# 467444_130_3_2-A.net
KiCad netlist of a schematic drawn in Altium Designer
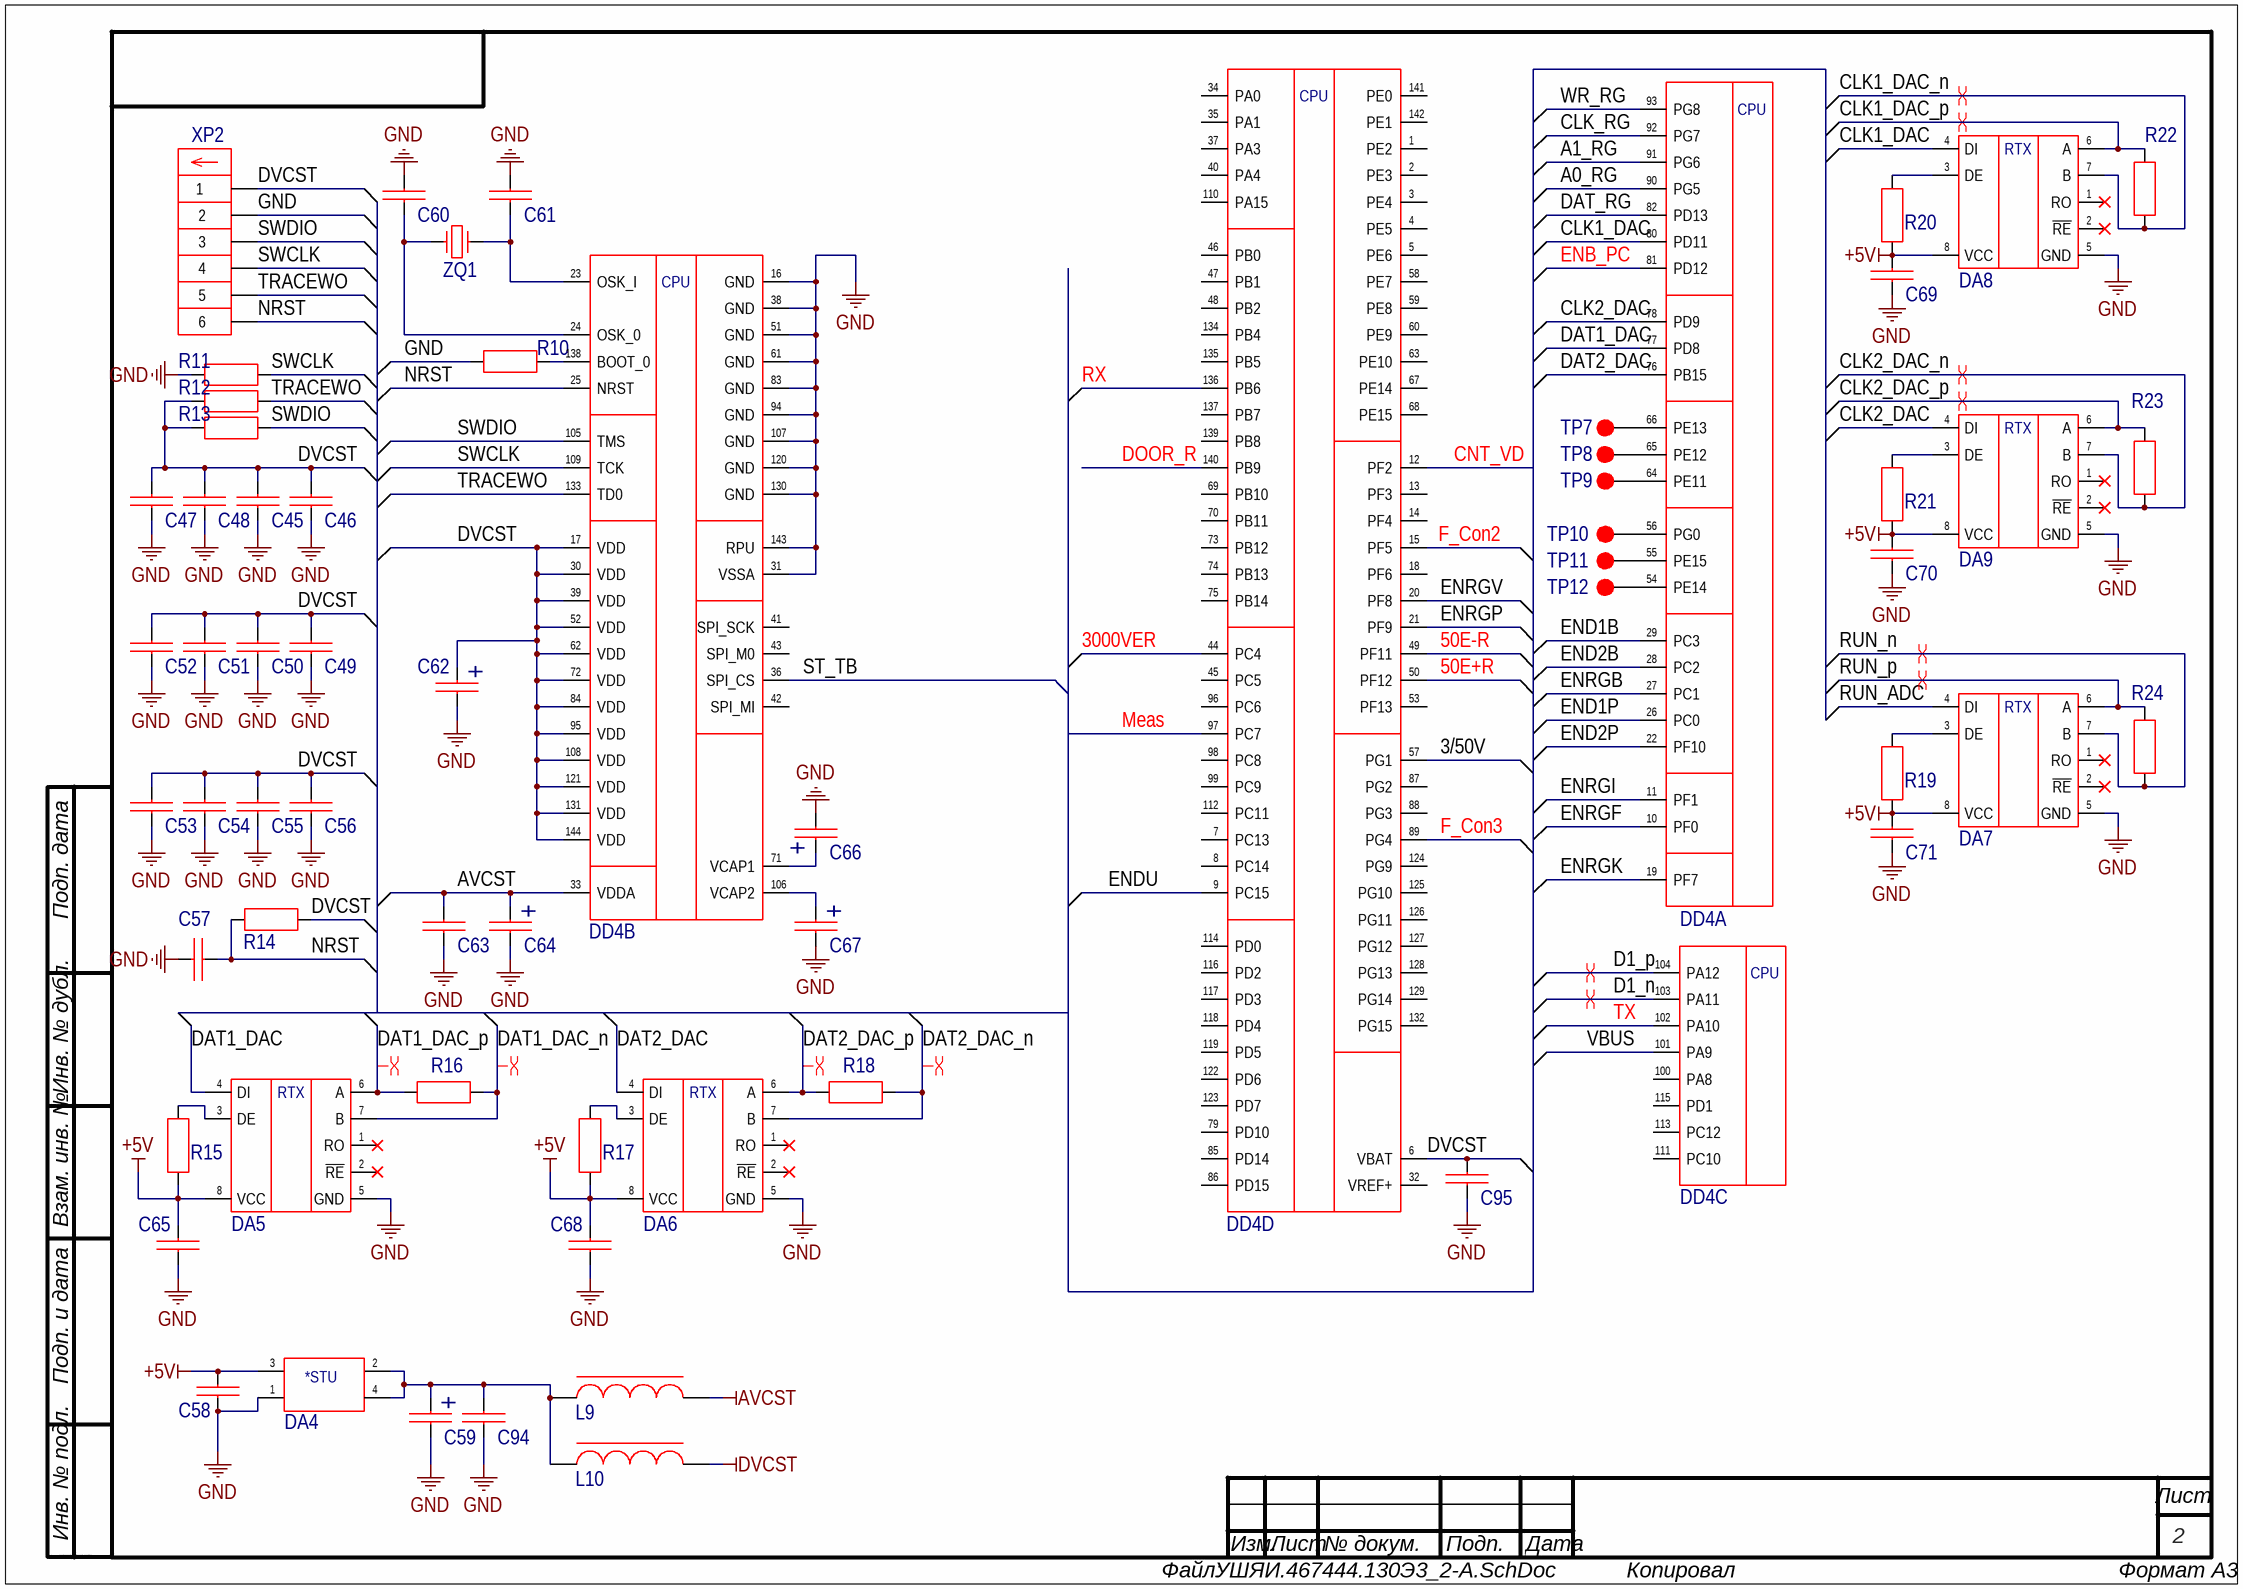
[diagram p0: УШЯИ.467444.130Э3_2-A.SchDoc]

(export (version "E")
  (design (tool "Eeschema 10.0.6"))
  (components
    (comp (ref "C45")
      (value "0,1 µF")
      (footprint "C_0805 [2012 Metric]")
      (description "Неполярный конденсатор")
      (fields (field (name "MANUFACTURER") "Murata") (field (name "VOLTAGE") "50V"))
      (libsource (lib "lib") (part "C_const"))
    )
    (comp (ref "C46")
      (value "0,1 µF")
      (footprint "C_0805 [2012 Metric]")
      (description "Неполярный конденсатор")
      (fields (field (name "MANUFACTURER") "Murata") (field (name "VOLTAGE") "50V"))
      (libsource (lib "lib") (part "C_const"))
    )
    (comp (ref "C47")
      (value "0,1 µF")
      (footprint "C_0805 [2012 Metric]")
      (description "Неполярный конденсатор")
      (fields (field (name "MANUFACTURER") "Murata") (field (name "VOLTAGE") "50V"))
      (libsource (lib "lib") (part "C_const"))
    )
    (comp (ref "C48")
      (value "0,1 µF")
      (footprint "C_0805 [2012 Metric]")
      (description "Неполярный конденсатор")
      (fields (field (name "MANUFACTURER") "Murata") (field (name "VOLTAGE") "50V"))
      (libsource (lib "lib") (part "C_const"))
    )
    (comp (ref "C49")
      (value "0,1 µF")
      (footprint "C_0805 [2012 Metric]")
      (description "Неполярный конденсатор")
      (fields (field (name "MANUFACTURER") "Murata") (field (name "VOLTAGE") "50V"))
      (libsource (lib "lib") (part "C_const"))
    )
    (comp (ref "C50")
      (value "0,1 µF")
      (footprint "C_0805 [2012 Metric]")
      (description "Неполярный конденсатор")
      (fields (field (name "MANUFACTURER") "Murata") (field (name "VOLTAGE") "50V"))
      (libsource (lib "lib") (part "C_const"))
    )
    (comp (ref "C51")
      (value "0,1 µF")
      (footprint "C_0805 [2012 Metric]")
      (description "Неполярный конденсатор")
      (fields (field (name "MANUFACTURER") "Murata") (field (name "VOLTAGE") "50V"))
      (libsource (lib "lib") (part "C_const"))
    )
    (comp (ref "C52")
      (value "0,1 µF")
      (footprint "C_0805 [2012 Metric]")
      (description "Неполярный конденсатор")
      (fields (field (name "MANUFACTURER") "Murata") (field (name "VOLTAGE") "50V"))
      (libsource (lib "lib") (part "C_const"))
    )
    (comp (ref "C53")
      (value "0,1 µF")
      (footprint "C_0805 [2012 Metric]")
      (description "Неполярный конденсатор")
      (fields (field (name "MANUFACTURER") "Murata") (field (name "VOLTAGE") "50V"))
      (libsource (lib "lib") (part "C_const"))
    )
    (comp (ref "C54")
      (value "0,1 µF")
      (footprint "C_0805 [2012 Metric]")
      (description "Неполярный конденсатор")
      (fields (field (name "MANUFACTURER") "Murata") (field (name "VOLTAGE") "50V"))
      (libsource (lib "lib") (part "C_const"))
    )
    (comp (ref "C55")
      (value "0,1 µF")
      (footprint "C_0805 [2012 Metric]")
      (description "Неполярный конденсатор")
      (fields (field (name "MANUFACTURER") "Murata") (field (name "VOLTAGE") "50V"))
      (libsource (lib "lib") (part "C_const"))
    )
    (comp (ref "C56")
      (value "0,1 µF")
      (footprint "C_0805 [2012 Metric]")
      (description "Неполярный конденсатор")
      (fields (field (name "MANUFACTURER") "Murata") (field (name "VOLTAGE") "50V"))
      (libsource (lib "lib") (part "C_const"))
    )
    (comp (ref "C57")
      (value "0,1 µF")
      (footprint "C_0805 [2012 Metric]")
      (description "Неполярный конденсатор")
      (fields (field (name "MANUFACTURER") "Murata") (field (name "VOLTAGE") "50V"))
      (libsource (lib "lib") (part "C_const"))
    )
    (comp (ref "C58")
      (value "0,1 µF")
      (footprint "C_0805 [2012 Metric]")
      (description "Неполярный конденсатор")
      (fields (field (name "MANUFACTURER") "Murata") (field (name "VOLTAGE") "50V"))
      (libsource (lib "lib") (part "C_const"))
    )
    (comp (ref "C59")
      (value "4,7 µF")
      (footprint "C+_1210 [3528-21 Metric]")
      (description "Полярный конденсатор")
      (fields (field (name "MANUFACTURER") "KYOCERA AVX") (field (name "VOLTAGE") "20V\r\n10V"))
      (libsource (lib "lib") (part "C_electrolytic"))
    )
    (comp (ref "C60")
      (value "20 pF")
      (footprint "C_0805 [2012 Metric]")
      (description "Неполярный конденсатор")
      (fields (field (name "MANUFACTURER") "Murata") (field (name "VOLTAGE") "50V"))
      (libsource (lib "lib") (part "C_const"))
    )
    (comp (ref "C61")
      (value "20 pF")
      (footprint "C_0805 [2012 Metric]")
      (description "Неполярный конденсатор")
      (fields (field (name "MANUFACTURER") "Murata") (field (name "VOLTAGE") "50V"))
      (libsource (lib "lib") (part "C_const"))
    )
    (comp (ref "C62")
      (value "10 µF")
      (footprint "C+_1210 [3528-21 Metric]")
      (description "Полярный конденсатор")
      (fields (field (name "MANUFACTURER") "KYOCERA AVX") (field (name "VOLTAGE") "20V\r\n10V"))
      (libsource (lib "lib") (part "C_electrolytic"))
    )
    (comp (ref "C63")
      (value "0,1 µF")
      (footprint "C_0805 [2012 Metric]")
      (description "Неполярный конденсатор")
      (fields (field (name "MANUFACTURER") "Murata") (field (name "VOLTAGE") "50V"))
      (libsource (lib "lib") (part "C_const"))
    )
    (comp (ref "C64")
      (value "10 µF")
      (footprint "C+_1210 [3528-21 Metric]")
      (description "Полярный конденсатор")
      (fields (field (name "MANUFACTURER") "KYOCERA AVX") (field (name "VOLTAGE") "20V\r\n10V"))
      (libsource (lib "lib") (part "C_electrolytic"))
    )
    (comp (ref "C65")
      (value "0,1 µF")
      (footprint "C_0805 [2012 Metric]")
      (description "Неполярный конденсатор")
      (fields (field (name "MANUFACTURER") "Murata") (field (name "VOLTAGE") "50V"))
      (libsource (lib "lib") (part "C_const"))
    )
    (comp (ref "C66")
      (value "2,2 µF")
      (footprint "C+_1206 [3216-18 Metric]")
      (description "Полярный конденсатор")
      (fields (field (name "MANUFACTURER") "AVX") (field (name "VOLTAGE") "16V\r\n10V"))
      (libsource (lib "lib") (part "C_electrolytic"))
    )
    (comp (ref "C67")
      (value "2,2 µF")
      (footprint "C+_1206 [3216-18 Metric]")
      (description "Полярный конденсатор")
      (fields (field (name "MANUFACTURER") "AVX") (field (name "VOLTAGE") "16V\r\n10V"))
      (libsource (lib "lib") (part "C_electrolytic"))
    )
    (comp (ref "C68")
      (value "0,1 µF")
      (footprint "C_0805 [2012 Metric]")
      (description "Неполярный конденсатор")
      (fields (field (name "MANUFACTURER") "Murata") (field (name "VOLTAGE") "50V"))
      (libsource (lib "lib") (part "C_const"))
    )
    (comp (ref "C69")
      (value "0,1 µF")
      (footprint "C_0805 [2012 Metric]")
      (description "Неполярный конденсатор")
      (fields (field (name "MANUFACTURER") "Murata") (field (name "VOLTAGE") "50V"))
      (libsource (lib "lib") (part "C_const"))
    )
    (comp (ref "C70")
      (value "0,1 µF")
      (footprint "C_0805 [2012 Metric]")
      (description "Неполярный конденсатор")
      (fields (field (name "MANUFACTURER") "Murata") (field (name "VOLTAGE") "50V"))
      (libsource (lib "lib") (part "C_const"))
    )
    (comp (ref "C71")
      (value "0,1 µF")
      (footprint "C_0805 [2012 Metric]")
      (description "Неполярный конденсатор")
      (fields (field (name "MANUFACTURER") "Murata") (field (name "VOLTAGE") "50V"))
      (libsource (lib "lib") (part "C_const"))
    )
    (comp (ref "C94")
      (value "0,1 µF")
      (footprint "C_0805 [2012 Metric]")
      (description "Неполярный конденсатор")
      (fields (field (name "MANUFACTURER") "Murata") (field (name "VOLTAGE") "25V"))
      (libsource (lib "lib") (part "C_const"))
    )
    (comp (ref "C95")
      (value "0,1 µF")
      (footprint "C_0805 [2012 Metric]")
      (description "Неполярный конденсатор")
      (fields (field (name "MANUFACTURER") "Murata") (field (name "VOLTAGE") "50V"))
      (libsource (lib "lib") (part "C_const"))
    )
    (comp (ref "DA4")
      (value "LD1117AS33TR")
      (footprint "SOT-223")
      (description "IC, Fixed LDO Voltage Regulator, 5.3V to 10V, 1.15V Dropout, 3.3Vout, 1Aout")
      (fields (field (name "MANUFACTURER") "STMicroelectronics"))
      (libsource (lib "lib") (part "VolReg_LD1117AS33TR"))
    )
    (comp (ref "DA5")
      (value "ADM483AR")
      (footprint "SOIC-8_1.27_5x4x1.75")
      (description "IC, Transceiver, RS422/RS485, 1 Driver, 1 Receiver, 4.75 V to 5.25 V, -40°C to 125°C")
      (fields (field (name "MANUFACTURER") "Analog Devices"))
      (libsource (lib "lib") (part "ADM483"))
    )
    (comp (ref "DA6")
      (value "ADM483AR")
      (footprint "SOIC-8_1.27_5x4x1.75")
      (description "IC, Transceiver, RS422/RS485, 1 Driver, 1 Receiver, 4.75 V to 5.25 V, -40°C to 125°C")
      (fields (field (name "MANUFACTURER") "Analog Devices"))
      (libsource (lib "lib") (part "ADM483"))
    )
    (comp (ref "DA7")
      (value "ADM483AR")
      (footprint "SOIC-8_1.27_5x4x1.75")
      (description "IC, Transceiver, RS422/RS485, 1 Driver, 1 Receiver, 4.75 V to 5.25 V, -40°C to 125°C")
      (fields (field (name "MANUFACTURER") "Analog Devices"))
      (libsource (lib "lib") (part "ADM483"))
    )
    (comp (ref "DA8")
      (value "ADM483AR")
      (footprint "SOIC-8_1.27_5x4x1.75")
      (description "IC, Transceiver, RS422/RS485, 1 Driver, 1 Receiver, 4.75 V to 5.25 V, -40°C to 125°C")
      (fields (field (name "MANUFACTURER") "Analog Devices"))
      (libsource (lib "lib") (part "ADM483"))
    )
    (comp (ref "DA9")
      (value "ADM483AR")
      (footprint "SOIC-8_1.27_5x4x1.75")
      (description "IC, Transceiver, RS422/RS485, 1 Driver, 1 Receiver, 4.75 V to 5.25 V, -40°C to 125°C")
      (fields (field (name "MANUFACTURER") "Analog Devices"))
      (libsource (lib "lib") (part "ADM483"))
    )
    (comp (ref "DD4")
      (value "STM32F429VIT6STM32F407ZGTx")
      (footprint "QFP-144[20x20]_0.5_22x22x1.6")
      (description "IC, ARM Cortex-M4, 168 MHz, 1 MB ROM, 192 kB RAM, -40°C to 85°C")
      (fields (field (name "MANUFACTURER") "STMicroelectronics"))
      (libsource (lib "lib") (part "STM32F407"))
    )
    (comp (ref "L9")
      (value "~")
      (footprint "IND_0805 [2012 Metric]")
      (fields (field (name "MANUFACTURER") "Vishay") (field (name "TOLERANCE") "±25%"))
      (libsource (lib "lib") (part "IND_ferromagnetic/ferrite_core"))
    )
    (comp (ref "L10")
      (value "~")
      (footprint "IND_0805 [2012 Metric]")
      (fields (field (name "MANUFACTURER") "Vishay") (field (name "TOLERANCE") "±25%"))
      (libsource (lib "lib") (part "IND_ferromagnetic/ferrite_core"))
    )
    (comp (ref "R10")
      (value "10k")
      (footprint "R_0805 [2012 Metric]")
      (fields (field (name "TOLERANCE") "±5%"))
      (libsource (lib "lib") (part "R_Const"))
    )
    (comp (ref "R11")
      (value "10k")
      (footprint "R_0805 [2012 Metric]")
      (fields (field (name "TOLERANCE") "±5%"))
      (libsource (lib "lib") (part "R_Const"))
    )
    (comp (ref "R12")
      (value "10k")
      (footprint "R_0805 [2012 Metric]")
      (fields (field (name "TOLERANCE") "±5%"))
      (libsource (lib "lib") (part "R_Const"))
    )
    (comp (ref "R13")
      (value "10k")
      (footprint "R_0805 [2012 Metric]")
      (fields (field (name "TOLERANCE") "±5%"))
      (libsource (lib "lib") (part "R_Const"))
    )
    (comp (ref "R14")
      (value "10k")
      (footprint "R_0805 [2012 Metric]")
      (fields (field (name "TOLERANCE") "±5%"))
      (libsource (lib "lib") (part "R_Const"))
    )
    (comp (ref "R15")
      (value "10k")
      (footprint "R_0805 [2012 Metric]")
      (fields (field (name "TOLERANCE") "±5%"))
      (libsource (lib "lib") (part "R_Const"))
    )
    (comp (ref "R16")
      (value "100R")
      (footprint "R_0805 [2012 Metric]")
      (fields (field (name "TOLERANCE") "±5%"))
      (libsource (lib "lib") (part "R_Const"))
    )
    (comp (ref "R17")
      (value "10k")
      (footprint "R_0805 [2012 Metric]")
      (fields (field (name "TOLERANCE") "±5%"))
      (libsource (lib "lib") (part "R_Const"))
    )
    (comp (ref "R18")
      (value "100R")
      (footprint "R_0805 [2012 Metric]")
      (fields (field (name "TOLERANCE") "±5%"))
      (libsource (lib "lib") (part "R_Const"))
    )
    (comp (ref "R19")
      (value "10k")
      (footprint "R_0805 [2012 Metric]")
      (fields (field (name "TOLERANCE") "±5%"))
      (libsource (lib "lib") (part "R_Const"))
    )
    (comp (ref "R20")
      (value "10k")
      (footprint "R_0805 [2012 Metric]")
      (fields (field (name "TOLERANCE") "±5%"))
      (libsource (lib "lib") (part "R_Const"))
    )
    (comp (ref "R21")
      (value "10k")
      (footprint "R_0805 [2012 Metric]")
      (fields (field (name "TOLERANCE") "±5%"))
      (libsource (lib "lib") (part "R_Const"))
    )
    (comp (ref "R22")
      (value "100R")
      (footprint "R_0805 [2012 Metric]")
      (fields (field (name "TOLERANCE") "±5%"))
      (libsource (lib "lib") (part "R_Const"))
    )
    (comp (ref "R23")
      (value "100R")
      (footprint "R_0805 [2012 Metric]")
      (fields (field (name "TOLERANCE") "±5%"))
      (libsource (lib "lib") (part "R_Const"))
    )
    (comp (ref "R24")
      (value "100R")
      (footprint "R_0805 [2012 Metric]")
      (fields (field (name "TOLERANCE") "±5%"))
      (libsource (lib "lib") (part "R_Const"))
    )
    (comp (ref "TP7") (value "~") (footprint "DSP_1.3") (libsource (lib "lib") (part "TP")))
    (comp (ref "TP8") (value "~") (footprint "DSP_1.3") (libsource (lib "lib") (part "TP")))
    (comp (ref "TP9") (value "~") (footprint "DSP_1.3") (libsource (lib "lib") (part "TP")))
    (comp (ref "TP10") (value "~") (footprint "DSP_1.3") (libsource (lib "lib") (part "TP")))
    (comp (ref "TP11") (value "~") (footprint "DSP_1.3") (libsource (lib "lib") (part "TP")))
    (comp (ref "TP12") (value "~") (footprint "DSP_1.3") (libsource (lib "lib") (part "TP")))
    (comp (ref "XP2")
      (value "AMPMODU II 280372-2")
      (footprint "AMP II-280372-2")
      (description "Male, 6 pin, 1 row, Vertical, Board-to-Board, 2.54 mm")
      (fields (field (name "MANUFACTURER") "TE Connectivity"))
      (libsource (lib "lib") (part "M_6"))
    )
    (comp (ref "ZQ1")
      (value "Q 25.0JXS63-12-30/30-FU")
      (footprint "JXS63")
      (fields (field (name "MANUFACTURER") "Jauch Quartz GmbH"))
      (libsource (lib "lib") (part "Rezonator_JXS63"))
    )
  )
  (nets
    (net (code "1") (name "+5V") (class "Default")
      (node (ref "C58") (pin "1") (pinfunction "1_1") (pintype "passive"))
      (node (ref "C65") (pin "2") (pinfunction "2_2") (pintype "passive"))
      (node (ref "C68") (pin "2") (pinfunction "2_2") (pintype "passive"))
      (node (ref "C69") (pin "2") (pinfunction "2_2") (pintype "passive"))
      (node (ref "C70") (pin "2") (pinfunction "2_2") (pintype "passive"))
      (node (ref "C71") (pin "2") (pinfunction "2_2") (pintype "passive"))
      (node (ref "DA4") (pin "3") (pinfunction "VIN_3") (pintype "passive"))
      (node (ref "DA5") (pin "8") (pinfunction "VCC_8") (pintype "passive"))
      (node (ref "DA6") (pin "8") (pinfunction "VCC_8") (pintype "passive"))
      (node (ref "DA7") (pin "8") (pinfunction "VCC_8") (pintype "passive"))
      (node (ref "DA8") (pin "8") (pinfunction "VCC_8") (pintype "passive"))
      (node (ref "DA9") (pin "8") (pinfunction "VCC_8") (pintype "passive"))
      (node (ref "R15") (pin "1") (pinfunction "1_1") (pintype "passive"))
      (node (ref "R17") (pin "1") (pinfunction "1_1") (pintype "passive"))
      (node (ref "R19") (pin "1") (pinfunction "1_1") (pintype "passive"))
      (node (ref "R20") (pin "1") (pinfunction "1_1") (pintype "passive"))
      (node (ref "R21") (pin "1") (pinfunction "1_1") (pintype "passive"))
    )
    (net (code "2") (name "/3{slash}50V") (class "Default")
      (node (ref "DD4") (pin "57") (pinfunction "PG1_57") (pintype "passive"))
    )
    (net (code "3") (name "/50E+R") (class "Default")
      (node (ref "DD4") (pin "50") (pinfunction "PF12_50") (pintype "passive"))
    )
    (net (code "4") (name "/50E-R") (class "Default")
      (node (ref "DD4") (pin "49") (pinfunction "PF11_49") (pintype "passive"))
    )
    (net (code "5") (name "/3000VER") (class "Default")
      (node (ref "DD4") (pin "44") (pinfunction "PC4_44") (pintype "passive"))
    )
    (net (code "6") (name "/A0_RG") (class "Default")
      (node (ref "DD4") (pin "90") (pinfunction "PG5_90") (pintype "passive"))
    )
    (net (code "7") (name "/A1_RG") (class "Default")
      (node (ref "DD4") (pin "91") (pinfunction "PG6_91") (pintype "passive"))
    )
    (net (code "8") (name "/CLK1_DAC") (class "Default")
      (node (ref "DA8") (pin "4") (pinfunction "DI_4") (pintype "passive"))
      (node (ref "DD4") (pin "80") (pinfunction "PD11_80") (pintype "passive"))
    )
    (net (code "9") (name "/CLK1_DAC_n") (class "Default")
      (node (ref "DA8") (pin "7") (pinfunction "B_7") (pintype "passive"))
      (node (ref "R22") (pin "1") (pinfunction "1_1") (pintype "passive"))
    )
    (net (code "10") (name "/CLK1_DAC_p") (class "Default")
      (node (ref "DA8") (pin "6") (pinfunction "A_6") (pintype "passive"))
      (node (ref "R22") (pin "2") (pinfunction "2_2") (pintype "passive"))
    )
    (net (code "11") (name "/CLK2_DAC") (class "Default")
      (node (ref "DA9") (pin "4") (pinfunction "DI_4") (pintype "passive"))
      (node (ref "DD4") (pin "78") (pinfunction "PD9_78") (pintype "passive"))
    )
    (net (code "12") (name "/CLK2_DAC_n") (class "Default")
      (node (ref "DA9") (pin "7") (pinfunction "B_7") (pintype "passive"))
      (node (ref "R23") (pin "1") (pinfunction "1_1") (pintype "passive"))
    )
    (net (code "13") (name "/CLK2_DAC_p") (class "Default")
      (node (ref "DA9") (pin "6") (pinfunction "A_6") (pintype "passive"))
      (node (ref "R23") (pin "2") (pinfunction "2_2") (pintype "passive"))
    )
    (net (code "14") (name "/CLK_RG") (class "Default")
      (node (ref "DD4") (pin "92") (pinfunction "PG7_92") (pintype "passive"))
    )
    (net (code "15") (name "/CNT_VD") (class "Default")
      (node (ref "DD4") (pin "12") (pinfunction "PF2_12") (pintype "passive"))
    )
    (net (code "16") (name "/D1_n") (class "Default")
      (node (ref "DD4") (pin "103") (pinfunction "PA11_103") (pintype "passive"))
    )
    (net (code "17") (name "/D1_p") (class "Default")
      (node (ref "DD4") (pin "104") (pinfunction "PA12_104") (pintype "passive"))
    )
    (net (code "18") (name "/DAT1_DAC") (class "Default")
      (node (ref "DA5") (pin "4") (pinfunction "DI_4") (pintype "passive"))
      (node (ref "DD4") (pin "77") (pinfunction "PD8_77") (pintype "passive"))
    )
    (net (code "19") (name "/DAT1_DAC_n") (class "Default")
      (node (ref "DA5") (pin "7") (pinfunction "B_7") (pintype "passive"))
      (node (ref "R16") (pin "2") (pinfunction "2_2") (pintype "passive"))
    )
    (net (code "20") (name "/DAT1_DAC_p") (class "Default")
      (node (ref "DA5") (pin "6") (pinfunction "A_6") (pintype "passive"))
      (node (ref "R16") (pin "1") (pinfunction "1_1") (pintype "passive"))
    )
    (net (code "21") (name "/DAT2_DAC") (class "Default")
      (node (ref "DA6") (pin "4") (pinfunction "DI_4") (pintype "passive"))
      (node (ref "DD4") (pin "76") (pinfunction "PB15_76") (pintype "passive"))
    )
    (net (code "22") (name "/DAT2_DAC_n") (class "Default")
      (node (ref "DA6") (pin "7") (pinfunction "B_7") (pintype "passive"))
      (node (ref "R18") (pin "2") (pinfunction "2_2") (pintype "passive"))
    )
    (net (code "23") (name "/DAT2_DAC_p") (class "Default")
      (node (ref "DA6") (pin "6") (pinfunction "A_6") (pintype "passive"))
      (node (ref "R18") (pin "1") (pinfunction "1_1") (pintype "passive"))
    )
    (net (code "24") (name "/DAT_RG") (class "Default")
      (node (ref "DD4") (pin "82") (pinfunction "PD13_82") (pintype "passive"))
    )
    (net (code "25") (name "/DOOR_R") (class "Default")
      (node (ref "DD4") (pin "140") (pinfunction "PB9_140") (pintype "passive"))
    )
    (net (code "26") (name "/ENB_PC") (class "Default")
      (node (ref "DD4") (pin "81") (pinfunction "PD12_81") (pintype "passive"))
    )
    (net (code "27") (name "/END1B") (class "Default")
      (node (ref "DD4") (pin "29") (pinfunction "PC3_29") (pintype "passive"))
    )
    (net (code "28") (name "/END1P") (class "Default")
      (node (ref "DD4") (pin "26") (pinfunction "PC0_26") (pintype "passive"))
    )
    (net (code "29") (name "/END2B") (class "Default")
      (node (ref "DD4") (pin "28") (pinfunction "PC2_28") (pintype "passive"))
    )
    (net (code "30") (name "/END2P") (class "Default")
      (node (ref "DD4") (pin "22") (pinfunction "PF10_22") (pintype "passive"))
    )
    (net (code "31") (name "/ENDU") (class "Default")
      (node (ref "DD4") (pin "9") (pinfunction "PC15_9") (pintype "passive"))
    )
    (net (code "32") (name "/ENRGB") (class "Default")
      (node (ref "DD4") (pin "27") (pinfunction "PC1_27") (pintype "passive"))
    )
    (net (code "33") (name "/ENRGF") (class "Default")
      (node (ref "DD4") (pin "10") (pinfunction "PF0_10") (pintype "passive"))
    )
    (net (code "34") (name "/ENRGI") (class "Default")
      (node (ref "DD4") (pin "11") (pinfunction "PF1_11") (pintype "passive"))
    )
    (net (code "35") (name "/ENRGK") (class "Default")
      (node (ref "DD4") (pin "19") (pinfunction "PF7_19") (pintype "passive"))
    )
    (net (code "36") (name "/ENRGP") (class "Default")
      (node (ref "DD4") (pin "21") (pinfunction "PF9_21") (pintype "passive"))
    )
    (net (code "37") (name "/ENRGV") (class "Default")
      (node (ref "DD4") (pin "20") (pinfunction "PF8_20") (pintype "passive"))
    )
    (net (code "38") (name "/F_Con2") (class "Default")
      (node (ref "DD4") (pin "15") (pinfunction "PF5_15") (pintype "passive"))
    )
    (net (code "39") (name "/F_Con3") (class "Default")
      (node (ref "DD4") (pin "89") (pinfunction "PG4_89") (pintype "passive"))
    )
    (net (code "40") (name "/Meas") (class "Default")
      (node (ref "DD4") (pin "97") (pinfunction "PC7_97") (pintype "passive"))
    )
    (net (code "41") (name "/NRST") (class "Default")
      (node (ref "C57") (pin "2") (pinfunction "2_2") (pintype "passive"))
      (node (ref "DD4") (pin "25") (pinfunction "NRST_25") (pintype "passive"))
      (node (ref "R14") (pin "2") (pinfunction "2_2") (pintype "passive"))
      (node (ref "XP2") (pin "6") (pinfunction "6_6") (pintype "passive"))
    )
    (net (code "42") (name "/RUN_ADC") (class "Default")
      (node (ref "DA7") (pin "4") (pinfunction "DI_4") (pintype "passive"))
    )
    (net (code "43") (name "/RUN_n") (class "Default")
      (node (ref "DA7") (pin "7") (pinfunction "B_7") (pintype "passive"))
      (node (ref "R24") (pin "1") (pinfunction "1_1") (pintype "passive"))
    )
    (net (code "44") (name "/RUN_p") (class "Default")
      (node (ref "DA7") (pin "6") (pinfunction "A_6") (pintype "passive"))
      (node (ref "R24") (pin "2") (pinfunction "2_2") (pintype "passive"))
    )
    (net (code "45") (name "/RX") (class "Default")
      (node (ref "DD4") (pin "136") (pinfunction "PB6_136") (pintype "passive"))
    )
    (net (code "46") (name "/ST_TB") (class "Default")
      (node (ref "DD4") (pin "36") (pinfunction "SPI_CS_36") (pintype "passive"))
    )
    (net (code "47") (name "/SWCLK") (class "Default")
      (node (ref "DD4") (pin "109") (pinfunction "TCK_109") (pintype "passive"))
      (node (ref "R11") (pin "2") (pinfunction "2_2") (pintype "passive"))
      (node (ref "XP2") (pin "4") (pinfunction "4_4") (pintype "passive"))
    )
    (net (code "48") (name "/SWDIO") (class "Default")
      (node (ref "DD4") (pin "105") (pinfunction "TMS_105") (pintype "passive"))
      (node (ref "R13") (pin "2") (pinfunction "2_2") (pintype "passive"))
      (node (ref "XP2") (pin "3") (pinfunction "3_3") (pintype "passive"))
    )
    (net (code "49") (name "/TRACEWO") (class "Default")
      (node (ref "DD4") (pin "133") (pinfunction "TD0_133") (pintype "passive"))
      (node (ref "R12") (pin "2") (pinfunction "2_2") (pintype "passive"))
      (node (ref "XP2") (pin "5") (pinfunction "5_5") (pintype "passive"))
    )
    (net (code "50") (name "/TX") (class "Default")
      (node (ref "DD4") (pin "102") (pinfunction "PA10_102") (pintype "passive"))
    )
    (net (code "51") (name "/VBUS") (class "Default")
      (node (ref "DD4") (pin "101") (pinfunction "PA9_101") (pintype "passive"))
    )
    (net (code "52") (name "/WR_RG") (class "Default")
      (node (ref "DD4") (pin "93") (pinfunction "PG8_93") (pintype "passive"))
    )
    (net (code "53") (name "AVCST") (class "Default")
      (node (ref "C63") (pin "2") (pinfunction "2_2") (pintype "passive"))
      (node (ref "C64") (pin "+") (pinfunction "+_+") (pintype "passive"))
      (node (ref "DD4") (pin "33") (pinfunction "VDDA_33") (pintype "passive"))
      (node (ref "L9") (pin "2") (pinfunction "2_2") (pintype "passive"))
    )
    (net (code "54") (name "DVCST") (class "Default")
      (node (ref "C45") (pin "2") (pinfunction "2_2") (pintype "passive"))
      (node (ref "C46") (pin "2") (pinfunction "2_2") (pintype "passive"))
      (node (ref "C47") (pin "2") (pinfunction "2_2") (pintype "passive"))
      (node (ref "C48") (pin "2") (pinfunction "2_2") (pintype "passive"))
      (node (ref "C49") (pin "2") (pinfunction "2_2") (pintype "passive"))
      (node (ref "C50") (pin "2") (pinfunction "2_2") (pintype "passive"))
      (node (ref "C51") (pin "2") (pinfunction "2_2") (pintype "passive"))
      (node (ref "C52") (pin "2") (pinfunction "2_2") (pintype "passive"))
      (node (ref "C53") (pin "2") (pinfunction "2_2") (pintype "passive"))
      (node (ref "C54") (pin "2") (pinfunction "2_2") (pintype "passive"))
      (node (ref "C55") (pin "2") (pinfunction "2_2") (pintype "passive"))
      (node (ref "C56") (pin "2") (pinfunction "2_2") (pintype "passive"))
      (node (ref "C62") (pin "+") (pinfunction "+_+") (pintype "passive"))
      (node (ref "C95") (pin "2") (pinfunction "2_2") (pintype "passive"))
      (node (ref "DD4") (pin "108") (pinfunction "VDD_108") (pintype "passive"))
      (node (ref "DD4") (pin "121") (pinfunction "VDD_121") (pintype "passive"))
      (node (ref "DD4") (pin "131") (pinfunction "VDD_131") (pintype "passive"))
      (node (ref "DD4") (pin "144") (pinfunction "VDD_144") (pintype "passive"))
      (node (ref "DD4") (pin "17") (pinfunction "VDD_17") (pintype "passive"))
      (node (ref "DD4") (pin "30") (pinfunction "VDD_30") (pintype "passive"))
      (node (ref "DD4") (pin "39") (pinfunction "VDD_39") (pintype "passive"))
      (node (ref "DD4") (pin "52") (pinfunction "VDD_52") (pintype "passive"))
      (node (ref "DD4") (pin "6") (pinfunction "VBAT_6") (pintype "passive"))
      (node (ref "DD4") (pin "62") (pinfunction "VDD_62") (pintype "passive"))
      (node (ref "DD4") (pin "72") (pinfunction "VDD_72") (pintype "passive"))
      (node (ref "DD4") (pin "84") (pinfunction "VDD_84") (pintype "passive"))
      (node (ref "DD4") (pin "95") (pinfunction "VDD_95") (pintype "passive"))
      (node (ref "L10") (pin "2") (pinfunction "2_2") (pintype "passive"))
      (node (ref "R12") (pin "1") (pinfunction "1_1") (pintype "passive"))
      (node (ref "R13") (pin "1") (pinfunction "1_1") (pintype "passive"))
      (node (ref "R14") (pin "1") (pinfunction "1_1") (pintype "passive"))
      (node (ref "XP2") (pin "1") (pinfunction "1_1") (pintype "passive"))
    )
    (net (code "55") (name "GND") (class "Default")
      (node (ref "C45") (pin "1") (pinfunction "1_1") (pintype "passive"))
      (node (ref "C46") (pin "1") (pinfunction "1_1") (pintype "passive"))
      (node (ref "C47") (pin "1") (pinfunction "1_1") (pintype "passive"))
      (node (ref "C48") (pin "1") (pinfunction "1_1") (pintype "passive"))
      (node (ref "C49") (pin "1") (pinfunction "1_1") (pintype "passive"))
      (node (ref "C50") (pin "1") (pinfunction "1_1") (pintype "passive"))
      (node (ref "C51") (pin "1") (pinfunction "1_1") (pintype "passive"))
      (node (ref "C52") (pin "1") (pinfunction "1_1") (pintype "passive"))
      (node (ref "C53") (pin "1") (pinfunction "1_1") (pintype "passive"))
      (node (ref "C54") (pin "1") (pinfunction "1_1") (pintype "passive"))
      (node (ref "C55") (pin "1") (pinfunction "1_1") (pintype "passive"))
      (node (ref "C56") (pin "1") (pinfunction "1_1") (pintype "passive"))
      (node (ref "C57") (pin "1") (pinfunction "1_1") (pintype "passive"))
      (node (ref "C58") (pin "2") (pinfunction "2_2") (pintype "passive"))
      (node (ref "C59") (pin "-") (pinfunction "-_-") (pintype "passive"))
      (node (ref "C60") (pin "2") (pinfunction "2_2") (pintype "passive"))
      (node (ref "C61") (pin "2") (pinfunction "2_2") (pintype "passive"))
      (node (ref "C62") (pin "-") (pinfunction "-_-") (pintype "passive"))
      (node (ref "C63") (pin "1") (pinfunction "1_1") (pintype "passive"))
      (node (ref "C64") (pin "-") (pinfunction "-_-") (pintype "passive"))
      (node (ref "C65") (pin "1") (pinfunction "1_1") (pintype "passive"))
      (node (ref "C66") (pin "-") (pinfunction "-_-") (pintype "passive"))
      (node (ref "C67") (pin "-") (pinfunction "-_-") (pintype "passive"))
      (node (ref "C68") (pin "1") (pinfunction "1_1") (pintype "passive"))
      (node (ref "C69") (pin "1") (pinfunction "1_1") (pintype "passive"))
      (node (ref "C70") (pin "1") (pinfunction "1_1") (pintype "passive"))
      (node (ref "C71") (pin "1") (pinfunction "1_1") (pintype "passive"))
      (node (ref "C94") (pin "1") (pinfunction "1_1") (pintype "passive"))
      (node (ref "C95") (pin "1") (pinfunction "1_1") (pintype "passive"))
      (node (ref "DA4") (pin "1") (pinfunction "ADJ/GND_1") (pintype "passive"))
      (node (ref "DA5") (pin "5") (pinfunction "GND_5") (pintype "passive"))
      (node (ref "DA6") (pin "5") (pinfunction "GND_5") (pintype "passive"))
      (node (ref "DA7") (pin "5") (pinfunction "GND_5") (pintype "passive"))
      (node (ref "DA8") (pin "5") (pinfunction "GND_5") (pintype "passive"))
      (node (ref "DA9") (pin "5") (pinfunction "GND_5") (pintype "passive"))
      (node (ref "DD4") (pin "107") (pinfunction "GND_107") (pintype "passive"))
      (node (ref "DD4") (pin "120") (pinfunction "GND_120") (pintype "passive"))
      (node (ref "DD4") (pin "130") (pinfunction "GND_130") (pintype "passive"))
      (node (ref "DD4") (pin "143") (pinfunction "RPU_143") (pintype "passive"))
      (node (ref "DD4") (pin "16") (pinfunction "GND_16") (pintype "passive"))
      (node (ref "DD4") (pin "31") (pinfunction "VSSA_31") (pintype "passive"))
      (node (ref "DD4") (pin "38") (pinfunction "GND_38") (pintype "passive"))
      (node (ref "DD4") (pin "51") (pinfunction "GND_51") (pintype "passive"))
      (node (ref "DD4") (pin "61") (pinfunction "GND_61") (pintype "passive"))
      (node (ref "DD4") (pin "83") (pinfunction "GND_83") (pintype "passive"))
      (node (ref "DD4") (pin "94") (pinfunction "GND_94") (pintype "passive"))
      (node (ref "R10") (pin "1") (pinfunction "1_1") (pintype "passive"))
      (node (ref "R11") (pin "1") (pinfunction "1_1") (pintype "passive"))
      (node (ref "XP2") (pin "2") (pinfunction "2_2") (pintype "passive"))
    )
    (net (code "56") (name "Net-(C59-Pad+)") (class "Default")
      (node (ref "C59") (pin "+") (pinfunction "+_+") (pintype "passive"))
      (node (ref "C94") (pin "2") (pinfunction "2_2") (pintype "passive"))
      (node (ref "DA4") (pin "2") (pinfunction "VOUT_2") (pintype "passive"))
      (node (ref "DA4") (pin "4") (pinfunction "VOUT_4") (pintype "passive"))
      (node (ref "L10") (pin "1") (pinfunction "1_1") (pintype "passive"))
      (node (ref "L9") (pin "1") (pinfunction "1_1") (pintype "passive"))
    )
    (net (code "57") (name "Net-(DA5-DE)") (class "Default")
      (node (ref "DA5") (pin "3") (pinfunction "DE_3") (pintype "passive"))
      (node (ref "R15") (pin "2") (pinfunction "2_2") (pintype "passive"))
    )
    (net (code "58") (name "Net-(DA6-DE)") (class "Default")
      (node (ref "DA6") (pin "3") (pinfunction "DE_3") (pintype "passive"))
      (node (ref "R17") (pin "2") (pinfunction "2_2") (pintype "passive"))
    )
    (net (code "59") (name "Net-(DA7-DE)") (class "Default")
      (node (ref "DA7") (pin "3") (pinfunction "DE_3") (pintype "passive"))
      (node (ref "R19") (pin "2") (pinfunction "2_2") (pintype "passive"))
    )
    (net (code "60") (name "Net-(DA8-DE)") (class "Default")
      (node (ref "DA8") (pin "3") (pinfunction "DE_3") (pintype "passive"))
      (node (ref "R20") (pin "2") (pinfunction "2_2") (pintype "passive"))
    )
    (net (code "61") (name "Net-(DA9-DE)") (class "Default")
      (node (ref "DA9") (pin "3") (pinfunction "DE_3") (pintype "passive"))
      (node (ref "R21") (pin "2") (pinfunction "2_2") (pintype "passive"))
    )
    (net (code "62") (name "Net-(DD4A-PE11)") (class "Default")
      (node (ref "DD4") (pin "64") (pinfunction "PE11_64") (pintype "passive"))
      (node (ref "TP9") (pin "1") (pinfunction "1_1") (pintype "passive"))
    )
    (net (code "63") (name "Net-(DD4A-PE12)") (class "Default")
      (node (ref "DD4") (pin "65") (pinfunction "PE12_65") (pintype "passive"))
      (node (ref "TP8") (pin "1") (pinfunction "1_1") (pintype "passive"))
    )
    (net (code "64") (name "Net-(DD4A-PE13)") (class "Default")
      (node (ref "DD4") (pin "66") (pinfunction "PE13_66") (pintype "passive"))
      (node (ref "TP7") (pin "1") (pinfunction "1_1") (pintype "passive"))
    )
    (net (code "65") (name "Net-(DD4A-PE14)") (class "Default")
      (node (ref "DD4") (pin "54") (pinfunction "PE14_54") (pintype "passive"))
      (node (ref "TP12") (pin "1") (pinfunction "1_1") (pintype "passive"))
    )
    (net (code "66") (name "Net-(DD4A-PE15)") (class "Default")
      (node (ref "DD4") (pin "55") (pinfunction "PE15_55") (pintype "passive"))
      (node (ref "TP11") (pin "1") (pinfunction "1_1") (pintype "passive"))
    )
    (net (code "67") (name "Net-(DD4A-PG0)") (class "Default")
      (node (ref "DD4") (pin "56") (pinfunction "PG0_56") (pintype "passive"))
      (node (ref "TP10") (pin "1") (pinfunction "1_1") (pintype "passive"))
    )
    (net (code "68") (name "Net-(DD4B-BOOT_0)") (class "Default")
      (node (ref "DD4") (pin "138") (pinfunction "BOOT_0_138") (pintype "passive"))
      (node (ref "R10") (pin "2") (pinfunction "2_2") (pintype "passive"))
    )
    (net (code "69") (name "Net-(DD4B-OSK_0)") (class "Default")
      (node (ref "C60") (pin "1") (pinfunction "1_1") (pintype "passive"))
      (node (ref "DD4") (pin "24") (pinfunction "OSK_0_24") (pintype "passive"))
      (node (ref "ZQ1") (pin "1") (pinfunction "1_1") (pintype "passive"))
    )
    (net (code "70") (name "Net-(DD4B-OSK_I)") (class "Default")
      (node (ref "C61") (pin "1") (pinfunction "1_1") (pintype "passive"))
      (node (ref "DD4") (pin "23") (pinfunction "OSK_I_23") (pintype "passive"))
      (node (ref "ZQ1") (pin "3") (pinfunction "3_3") (pintype "passive"))
    )
    (net (code "71") (name "Net-(DD4B-VCAP1)") (class "Default")
      (node (ref "C66") (pin "+") (pinfunction "+_+") (pintype "passive"))
      (node (ref "DD4") (pin "71") (pinfunction "VCAP1_71") (pintype "passive"))
    )
    (net (code "72") (name "Net-(DD4B-VCAP2)") (class "Default")
      (node (ref "C67") (pin "+") (pinfunction "+_+") (pintype "passive"))
      (node (ref "DD4") (pin "106") (pinfunction "VCAP2_106") (pintype "passive"))
    )
    (net (code "73") (name "unconnected-(DA5-RO-Pad1)") (class "Default")
      (node (ref "DA5") (pin "1") (pinfunction "RO_1") (pintype "passive+no_connect"))
    )
    (net (code "74") (name "unconnected-(DA5-~{RE}-Pad2)") (class "Default")
      (node (ref "DA5") (pin "2") (pinfunction "~{RE}_2") (pintype "passive+no_connect"))
    )
    (net (code "75") (name "unconnected-(DA6-RO-Pad1)") (class "Default")
      (node (ref "DA6") (pin "1") (pinfunction "RO_1") (pintype "passive+no_connect"))
    )
    (net (code "76") (name "unconnected-(DA6-~{RE}-Pad2)") (class "Default")
      (node (ref "DA6") (pin "2") (pinfunction "~{RE}_2") (pintype "passive+no_connect"))
    )
    (net (code "77") (name "unconnected-(DA7-RO-Pad1)") (class "Default")
      (node (ref "DA7") (pin "1") (pinfunction "RO_1") (pintype "passive+no_connect"))
    )
    (net (code "78") (name "unconnected-(DA7-~{RE}-Pad2)") (class "Default")
      (node (ref "DA7") (pin "2") (pinfunction "~{RE}_2") (pintype "passive+no_connect"))
    )
    (net (code "79") (name "unconnected-(DA8-RO-Pad1)") (class "Default")
      (node (ref "DA8") (pin "1") (pinfunction "RO_1") (pintype "passive+no_connect"))
    )
    (net (code "80") (name "unconnected-(DA8-~{RE}-Pad2)") (class "Default")
      (node (ref "DA8") (pin "2") (pinfunction "~{RE}_2") (pintype "passive+no_connect"))
    )
    (net (code "81") (name "unconnected-(DA9-RO-Pad1)") (class "Default")
      (node (ref "DA9") (pin "1") (pinfunction "RO_1") (pintype "passive+no_connect"))
    )
    (net (code "82") (name "unconnected-(DA9-~{RE}-Pad2)") (class "Default")
      (node (ref "DA9") (pin "2") (pinfunction "~{RE}_2") (pintype "passive+no_connect"))
    )
    (net (code "83") (name "unconnected-(DD4B-SPI_M0-Pad43)") (class "Default")
      (node (ref "DD4") (pin "43") (pinfunction "SPI_M0_43") (pintype "passive"))
    )
    (net (code "84") (name "unconnected-(DD4B-SPI_MI-Pad42)") (class "Default")
      (node (ref "DD4") (pin "42") (pinfunction "SPI_MI_42") (pintype "passive"))
    )
    (net (code "85") (name "unconnected-(DD4B-SPI_SCK-Pad41)") (class "Default")
      (node (ref "DD4") (pin "41") (pinfunction "SPI_SCK_41") (pintype "passive"))
    )
    (net (code "86") (name "unconnected-(DD4C-PA8-Pad100)") (class "Default")
      (node (ref "DD4") (pin "100") (pinfunction "PA8_100") (pintype "passive"))
    )
    (net (code "87") (name "unconnected-(DD4C-PC10-Pad111)") (class "Default")
      (node (ref "DD4") (pin "111") (pinfunction "PC10_111") (pintype "passive"))
    )
    (net (code "88") (name "unconnected-(DD4C-PC12-Pad113)") (class "Default")
      (node (ref "DD4") (pin "113") (pinfunction "PC12_113") (pintype "passive"))
    )
    (net (code "89") (name "unconnected-(DD4C-PD1-Pad115)") (class "Default")
      (node (ref "DD4") (pin "115") (pinfunction "PD1_115") (pintype "passive"))
    )
    (net (code "90") (name "unconnected-(DD4D-PA0-Pad34)") (class "Default")
      (node (ref "DD4") (pin "34") (pinfunction "PA0_34") (pintype "passive"))
    )
    (net (code "91") (name "unconnected-(DD4D-PA1-Pad35)") (class "Default")
      (node (ref "DD4") (pin "35") (pinfunction "PA1_35") (pintype "passive"))
    )
    (net (code "92") (name "unconnected-(DD4D-PA3-Pad37)") (class "Default")
      (node (ref "DD4") (pin "37") (pinfunction "PA3_37") (pintype "passive"))
    )
    (net (code "93") (name "unconnected-(DD4D-PA4-Pad40)") (class "Default")
      (node (ref "DD4") (pin "40") (pinfunction "PA4_40") (pintype "passive"))
    )
    (net (code "94") (name "unconnected-(DD4D-PA15-Pad110)") (class "Default")
      (node (ref "DD4") (pin "110") (pinfunction "PA15_110") (pintype "passive"))
    )
    (net (code "95") (name "unconnected-(DD4D-PB0-Pad46)") (class "Default")
      (node (ref "DD4") (pin "46") (pinfunction "PB0_46") (pintype "passive"))
    )
    (net (code "96") (name "unconnected-(DD4D-PB1-Pad47)") (class "Default")
      (node (ref "DD4") (pin "47") (pinfunction "PB1_47") (pintype "passive"))
    )
    (net (code "97") (name "unconnected-(DD4D-PB2-Pad48)") (class "Default")
      (node (ref "DD4") (pin "48") (pinfunction "PB2_48") (pintype "passive"))
    )
    (net (code "98") (name "unconnected-(DD4D-PB4-Pad134)") (class "Default")
      (node (ref "DD4") (pin "134") (pinfunction "PB4_134") (pintype "passive"))
    )
    (net (code "99") (name "unconnected-(DD4D-PB5-Pad135)") (class "Default")
      (node (ref "DD4") (pin "135") (pinfunction "PB5_135") (pintype "passive"))
    )
    (net (code "100") (name "unconnected-(DD4D-PB7-Pad137)") (class "Default")
      (node (ref "DD4") (pin "137") (pinfunction "PB7_137") (pintype "passive"))
    )
    (net (code "101") (name "unconnected-(DD4D-PB8-Pad139)") (class "Default")
      (node (ref "DD4") (pin "139") (pinfunction "PB8_139") (pintype "passive"))
    )
    (net (code "102") (name "unconnected-(DD4D-PB10-Pad69)") (class "Default")
      (node (ref "DD4") (pin "69") (pinfunction "PB10_69") (pintype "passive"))
    )
    (net (code "103") (name "unconnected-(DD4D-PB11-Pad70)") (class "Default")
      (node (ref "DD4") (pin "70") (pinfunction "PB11_70") (pintype "passive"))
    )
    (net (code "104") (name "unconnected-(DD4D-PB12-Pad73)") (class "Default")
      (node (ref "DD4") (pin "73") (pinfunction "PB12_73") (pintype "passive"))
    )
    (net (code "105") (name "unconnected-(DD4D-PB13-Pad74)") (class "Default")
      (node (ref "DD4") (pin "74") (pinfunction "PB13_74") (pintype "passive"))
    )
    (net (code "106") (name "unconnected-(DD4D-PB14-Pad75)") (class "Default")
      (node (ref "DD4") (pin "75") (pinfunction "PB14_75") (pintype "passive"))
    )
    (net (code "107") (name "unconnected-(DD4D-PC5-Pad45)") (class "Default")
      (node (ref "DD4") (pin "45") (pinfunction "PC5_45") (pintype "passive"))
    )
    (net (code "108") (name "unconnected-(DD4D-PC6-Pad96)") (class "Default")
      (node (ref "DD4") (pin "96") (pinfunction "PC6_96") (pintype "passive"))
    )
    (net (code "109") (name "unconnected-(DD4D-PC8-Pad98)") (class "Default")
      (node (ref "DD4") (pin "98") (pinfunction "PC8_98") (pintype "passive"))
    )
    (net (code "110") (name "unconnected-(DD4D-PC9-Pad99)") (class "Default")
      (node (ref "DD4") (pin "99") (pinfunction "PC9_99") (pintype "passive"))
    )
    (net (code "111") (name "unconnected-(DD4D-PC11-Pad112)") (class "Default")
      (node (ref "DD4") (pin "112") (pinfunction "PC11_112") (pintype "passive"))
    )
    (net (code "112") (name "unconnected-(DD4D-PC13-Pad7)") (class "Default")
      (node (ref "DD4") (pin "7") (pinfunction "PC13_7") (pintype "passive"))
    )
    (net (code "113") (name "unconnected-(DD4D-PC14-Pad8)") (class "Default")
      (node (ref "DD4") (pin "8") (pinfunction "PC14_8") (pintype "passive"))
    )
    (net (code "114") (name "unconnected-(DD4D-PD0-Pad114)") (class "Default")
      (node (ref "DD4") (pin "114") (pinfunction "PD0_114") (pintype "passive"))
    )
    (net (code "115") (name "unconnected-(DD4D-PD2-Pad116)") (class "Default")
      (node (ref "DD4") (pin "116") (pinfunction "PD2_116") (pintype "passive"))
    )
    (net (code "116") (name "unconnected-(DD4D-PD3-Pad117)") (class "Default")
      (node (ref "DD4") (pin "117") (pinfunction "PD3_117") (pintype "passive"))
    )
    (net (code "117") (name "unconnected-(DD4D-PD4-Pad118)") (class "Default")
      (node (ref "DD4") (pin "118") (pinfunction "PD4_118") (pintype "passive"))
    )
    (net (code "118") (name "unconnected-(DD4D-PD5-Pad119)") (class "Default")
      (node (ref "DD4") (pin "119") (pinfunction "PD5_119") (pintype "passive"))
    )
    (net (code "119") (name "unconnected-(DD4D-PD6-Pad122)") (class "Default")
      (node (ref "DD4") (pin "122") (pinfunction "PD6_122") (pintype "passive"))
    )
    (net (code "120") (name "unconnected-(DD4D-PD7-Pad123)") (class "Default")
      (node (ref "DD4") (pin "123") (pinfunction "PD7_123") (pintype "passive"))
    )
    (net (code "121") (name "unconnected-(DD4D-PD10-Pad79)") (class "Default")
      (node (ref "DD4") (pin "79") (pinfunction "PD10_79") (pintype "passive"))
    )
    (net (code "122") (name "unconnected-(DD4D-PD14-Pad85)") (class "Default")
      (node (ref "DD4") (pin "85") (pinfunction "PD14_85") (pintype "passive"))
    )
    (net (code "123") (name "unconnected-(DD4D-PD15-Pad86)") (class "Default")
      (node (ref "DD4") (pin "86") (pinfunction "PD15_86") (pintype "passive"))
    )
    (net (code "124") (name "unconnected-(DD4D-PE0-Pad141)") (class "Default")
      (node (ref "DD4") (pin "141") (pinfunction "PE0_141") (pintype "passive"))
    )
    (net (code "125") (name "unconnected-(DD4D-PE1-Pad142)") (class "Default")
      (node (ref "DD4") (pin "142") (pinfunction "PE1_142") (pintype "passive"))
    )
    (net (code "126") (name "unconnected-(DD4D-PE2-Pad1)") (class "Default")
      (node (ref "DD4") (pin "1") (pinfunction "PE2_1") (pintype "passive"))
    )
    (net (code "127") (name "unconnected-(DD4D-PE3-Pad2)") (class "Default")
      (node (ref "DD4") (pin "2") (pinfunction "PE3_2") (pintype "passive"))
    )
    (net (code "128") (name "unconnected-(DD4D-PE4-Pad3)") (class "Default")
      (node (ref "DD4") (pin "3") (pinfunction "PE4_3") (pintype "passive"))
    )
    (net (code "129") (name "unconnected-(DD4D-PE5-Pad4)") (class "Default")
      (node (ref "DD4") (pin "4") (pinfunction "PE5_4") (pintype "passive"))
    )
    (net (code "130") (name "unconnected-(DD4D-PE6-Pad5)") (class "Default")
      (node (ref "DD4") (pin "5") (pinfunction "PE6_5") (pintype "passive"))
    )
    (net (code "131") (name "unconnected-(DD4D-PE7-Pad58)") (class "Default")
      (node (ref "DD4") (pin "58") (pinfunction "PE7_58") (pintype "passive"))
    )
    (net (code "132") (name "unconnected-(DD4D-PE8-Pad59)") (class "Default")
      (node (ref "DD4") (pin "59") (pinfunction "PE8_59") (pintype "passive"))
    )
    (net (code "133") (name "unconnected-(DD4D-PE9-Pad60)") (class "Default")
      (node (ref "DD4") (pin "60") (pinfunction "PE9_60") (pintype "passive"))
    )
    (net (code "134") (name "unconnected-(DD4D-PE10-Pad63)") (class "Default")
      (node (ref "DD4") (pin "63") (pinfunction "PE10_63") (pintype "passive"))
    )
    (net (code "135") (name "unconnected-(DD4D-PE14-Pad67)") (class "Default")
      (node (ref "DD4") (pin "67") (pinfunction "PE14_67") (pintype "passive"))
    )
    (net (code "136") (name "unconnected-(DD4D-PE15-Pad68)") (class "Default")
      (node (ref "DD4") (pin "68") (pinfunction "PE15_68") (pintype "passive"))
    )
    (net (code "137") (name "unconnected-(DD4D-PF3-Pad13)") (class "Default")
      (node (ref "DD4") (pin "13") (pinfunction "PF3_13") (pintype "passive"))
    )
    (net (code "138") (name "unconnected-(DD4D-PF4-Pad14)") (class "Default")
      (node (ref "DD4") (pin "14") (pinfunction "PF4_14") (pintype "passive"))
    )
    (net (code "139") (name "unconnected-(DD4D-PF6-Pad18)") (class "Default")
      (node (ref "DD4") (pin "18") (pinfunction "PF6_18") (pintype "passive"))
    )
    (net (code "140") (name "unconnected-(DD4D-PF13-Pad53)") (class "Default")
      (node (ref "DD4") (pin "53") (pinfunction "PF13_53") (pintype "passive"))
    )
    (net (code "141") (name "unconnected-(DD4D-PG2-Pad87)") (class "Default")
      (node (ref "DD4") (pin "87") (pinfunction "PG2_87") (pintype "passive"))
    )
    (net (code "142") (name "unconnected-(DD4D-PG3-Pad88)") (class "Default")
      (node (ref "DD4") (pin "88") (pinfunction "PG3_88") (pintype "passive"))
    )
    (net (code "143") (name "unconnected-(DD4D-PG9-Pad124)") (class "Default")
      (node (ref "DD4") (pin "124") (pinfunction "PG9_124") (pintype "passive"))
    )
    (net (code "144") (name "unconnected-(DD4D-PG10-Pad125)") (class "Default")
      (node (ref "DD4") (pin "125") (pinfunction "PG10_125") (pintype "passive"))
    )
    (net (code "145") (name "unconnected-(DD4D-PG11-Pad126)") (class "Default")
      (node (ref "DD4") (pin "126") (pinfunction "PG11_126") (pintype "passive"))
    )
    (net (code "146") (name "unconnected-(DD4D-PG12-Pad127)") (class "Default")
      (node (ref "DD4") (pin "127") (pinfunction "PG12_127") (pintype "passive"))
    )
    (net (code "147") (name "unconnected-(DD4D-PG13-Pad128)") (class "Default")
      (node (ref "DD4") (pin "128") (pinfunction "PG13_128") (pintype "passive"))
    )
    (net (code "148") (name "unconnected-(DD4D-PG14-Pad129)") (class "Default")
      (node (ref "DD4") (pin "129") (pinfunction "PG14_129") (pintype "passive"))
    )
    (net (code "149") (name "unconnected-(DD4D-PG15-Pad132)") (class "Default")
      (node (ref "DD4") (pin "132") (pinfunction "PG15_132") (pintype "passive"))
    )
    (net (code "150") (name "unconnected-(DD4D-VREF+-Pad32)") (class "Default")
      (node (ref "DD4") (pin "32") (pinfunction "VREF+_32") (pintype "passive"))
    )
  )
)
